# 07_-_FPGA_XCVR.net
KiCad netlist of a schematic drawn in Altium Designer
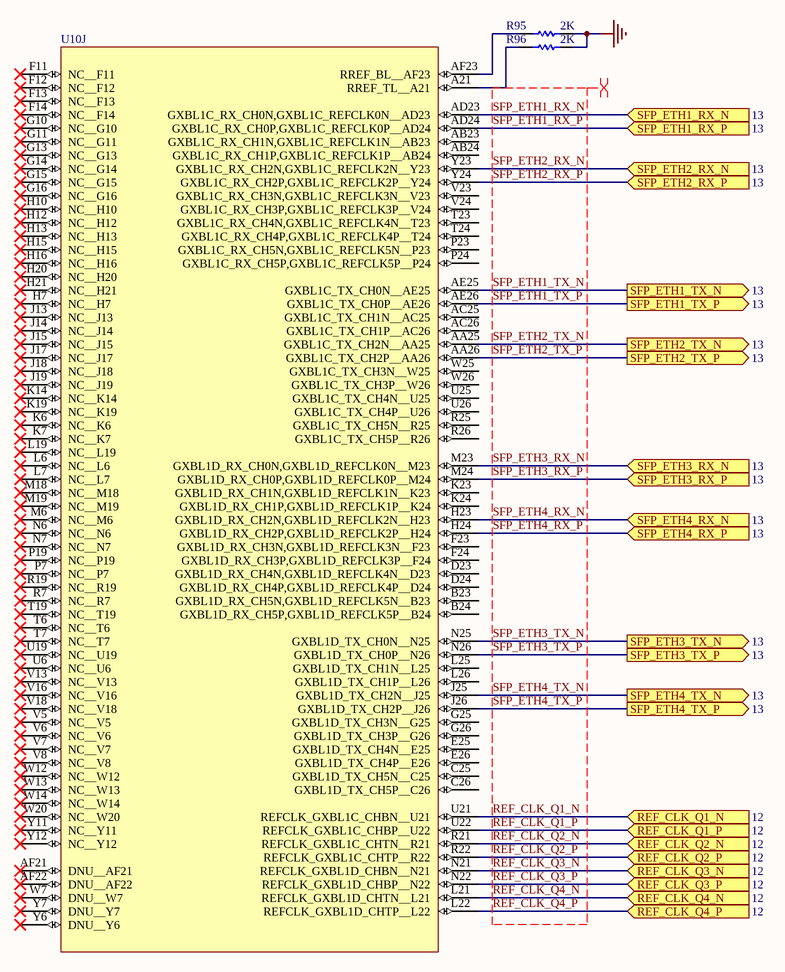
[diagram p0: [07] - FPGA XCVR.SchDoc]

(export (version "E")
  (design (tool "Eeschema 10.0.6"))
  (components
    (comp (ref "R95")
      (value "2K")
      (footprint "0402_R")
      (description "SMD Resistor")
      (fields (field (name "TOLERANCE") "1%"))
      (libsource (lib "Passive Components") (part "Res SMD"))
    )
    (comp (ref "R96")
      (value "2K")
      (footprint "0402_R")
      (description "SMD Resistor")
      (fields (field (name "TOLERANCE") "1%"))
      (libsource (lib "Passive Components") (part "Res SMD"))
    )
    (comp (ref "U10")
      (value "10AX016 F27")
      (footprint "FBGA672")
      (libsource (lib "Project_schlib") (part "10AX016"))
    )
  )
  (nets
    (net (code "1") (name "/REF_CLK_Q1_N") (class "Default")
      (node (ref "U10") (pin "U21") (pinfunction "REFCLK_GXBL1C_CHBN__U21_U21") (pintype "bidirectional"))
    )
    (net (code "2") (name "/REF_CLK_Q1_P") (class "Default")
      (node (ref "U10") (pin "U22") (pinfunction "REFCLK_GXBL1C_CHBP__U22_U22") (pintype "bidirectional"))
    )
    (net (code "3") (name "/REF_CLK_Q2_N") (class "Default")
      (node (ref "U10") (pin "R21") (pinfunction "REFCLK_GXBL1C_CHTN__R21_R21") (pintype "bidirectional"))
    )
    (net (code "4") (name "/REF_CLK_Q2_P") (class "Default")
      (node (ref "U10") (pin "R22") (pinfunction "REFCLK_GXBL1C_CHTP__R22_R22") (pintype "bidirectional"))
    )
    (net (code "5") (name "/REF_CLK_Q3_N") (class "Default")
      (node (ref "U10") (pin "N21") (pinfunction "REFCLK_GXBL1D_CHBN__N21_N21") (pintype "bidirectional"))
    )
    (net (code "6") (name "/REF_CLK_Q3_P") (class "Default")
      (node (ref "U10") (pin "N22") (pinfunction "REFCLK_GXBL1D_CHBP__N22_N22") (pintype "bidirectional"))
    )
    (net (code "7") (name "/REF_CLK_Q4_N") (class "Default")
      (node (ref "U10") (pin "L21") (pinfunction "REFCLK_GXBL1D_CHTN__L21_L21") (pintype "bidirectional"))
    )
    (net (code "8") (name "/REF_CLK_Q4_P") (class "Default")
      (node (ref "U10") (pin "L22") (pinfunction "REFCLK_GXBL1D_CHTP__L22_L22") (pintype "bidirectional"))
    )
    (net (code "9") (name "/SFP_ETH1_RX_N") (class "Default")
      (node (ref "U10") (pin "AD23") (pinfunction "GXBL1C_RX_CH0N,GXBL1C_REFCLK0N__AD23_AD23") (pintype "bidirectional"))
    )
    (net (code "10") (name "/SFP_ETH1_RX_P") (class "Default")
      (node (ref "U10") (pin "AD24") (pinfunction "GXBL1C_RX_CH0P,GXBL1C_REFCLK0P__AD24_AD24") (pintype "bidirectional"))
    )
    (net (code "11") (name "/SFP_ETH1_TX_N") (class "Default")
      (node (ref "U10") (pin "AE25") (pinfunction "GXBL1C_TX_CH0N__AE25_AE25") (pintype "bidirectional"))
    )
    (net (code "12") (name "/SFP_ETH1_TX_P") (class "Default")
      (node (ref "U10") (pin "AE26") (pinfunction "GXBL1C_TX_CH0P__AE26_AE26") (pintype "bidirectional"))
    )
    (net (code "13") (name "/SFP_ETH2_RX_N") (class "Default")
      (node (ref "U10") (pin "Y23") (pinfunction "GXBL1C_RX_CH2N,GXBL1C_REFCLK2N__Y23_Y23") (pintype "bidirectional"))
    )
    (net (code "14") (name "/SFP_ETH2_RX_P") (class "Default")
      (node (ref "U10") (pin "Y24") (pinfunction "GXBL1C_RX_CH2P,GXBL1C_REFCLK2P__Y24_Y24") (pintype "bidirectional"))
    )
    (net (code "15") (name "/SFP_ETH2_TX_N") (class "Default")
      (node (ref "U10") (pin "AA25") (pinfunction "GXBL1C_TX_CH2N__AA25_AA25") (pintype "bidirectional"))
    )
    (net (code "16") (name "/SFP_ETH2_TX_P") (class "Default")
      (node (ref "U10") (pin "AA26") (pinfunction "GXBL1C_TX_CH2P__AA26_AA26") (pintype "bidirectional"))
    )
    (net (code "17") (name "/SFP_ETH3_RX_N") (class "Default")
      (node (ref "U10") (pin "M23") (pinfunction "GXBL1D_RX_CH0N,GXBL1D_REFCLK0N__M23_M23") (pintype "bidirectional"))
    )
    (net (code "18") (name "/SFP_ETH3_RX_P") (class "Default")
      (node (ref "U10") (pin "M24") (pinfunction "GXBL1D_RX_CH0P,GXBL1D_REFCLK0P__M24_M24") (pintype "bidirectional"))
    )
    (net (code "19") (name "/SFP_ETH3_TX_N") (class "Default")
      (node (ref "U10") (pin "N25") (pinfunction "GXBL1D_TX_CH0N__N25_N25") (pintype "bidirectional"))
    )
    (net (code "20") (name "/SFP_ETH3_TX_P") (class "Default")
      (node (ref "U10") (pin "N26") (pinfunction "GXBL1D_TX_CH0P__N26_N26") (pintype "bidirectional"))
    )
    (net (code "21") (name "/SFP_ETH4_RX_N") (class "Default")
      (node (ref "U10") (pin "H23") (pinfunction "GXBL1D_RX_CH2N,GXBL1D_REFCLK2N__H23_H23") (pintype "bidirectional"))
    )
    (net (code "22") (name "/SFP_ETH4_RX_P") (class "Default")
      (node (ref "U10") (pin "H24") (pinfunction "GXBL1D_RX_CH2P,GXBL1D_REFCLK2P__H24_H24") (pintype "bidirectional"))
    )
    (net (code "23") (name "/SFP_ETH4_TX_N") (class "Default")
      (node (ref "U10") (pin "J25") (pinfunction "GXBL1D_TX_CH2N__J25_J25") (pintype "bidirectional"))
    )
    (net (code "24") (name "/SFP_ETH4_TX_P") (class "Default")
      (node (ref "U10") (pin "J26") (pinfunction "GXBL1D_TX_CH2P__J26_J26") (pintype "bidirectional"))
    )
    (net (code "25") (name "GND") (class "Default")
      (node (ref "R95") (pin "2") (pinfunction "2_2") (pintype "passive"))
      (node (ref "R96") (pin "2") (pinfunction "2_2") (pintype "passive"))
    )
    (net (code "26") (name "Net-(U10J-RREF_BL__AF23)") (class "Default")
      (node (ref "R95") (pin "1") (pinfunction "1_1") (pintype "passive"))
      (node (ref "U10") (pin "AF23") (pinfunction "RREF_BL__AF23_AF23") (pintype "bidirectional"))
    )
    (net (code "27") (name "Net-(U10J-RREF_TL__A21)") (class "Default")
      (node (ref "R96") (pin "1") (pinfunction "1_1") (pintype "passive"))
      (node (ref "U10") (pin "A21") (pinfunction "RREF_TL__A21_A21") (pintype "bidirectional"))
    )
    (net (code "28") (name "unconnected-(U10J-DNU__AF21-PadAF21)") (class "Default")
      (node (ref "U10") (pin "AF21") (pinfunction "DNU__AF21_AF21") (pintype "bidirectional+no_connect"))
    )
    (net (code "29") (name "unconnected-(U10J-DNU__AF22-PadAF22)") (class "Default")
      (node (ref "U10") (pin "AF22") (pinfunction "DNU__AF22_AF22") (pintype "bidirectional+no_connect"))
    )
    (net (code "30") (name "unconnected-(U10J-DNU__W7-PadW7)") (class "Default")
      (node (ref "U10") (pin "W7") (pinfunction "DNU__W7_W7") (pintype "bidirectional+no_connect"))
    )
    (net (code "31") (name "unconnected-(U10J-DNU__Y6-PadY6)") (class "Default")
      (node (ref "U10") (pin "Y6") (pinfunction "DNU__Y6_Y6") (pintype "bidirectional+no_connect"))
    )
    (net (code "32") (name "unconnected-(U10J-DNU__Y7-PadY7)") (class "Default")
      (node (ref "U10") (pin "Y7") (pinfunction "DNU__Y7_Y7") (pintype "bidirectional+no_connect"))
    )
    (net (code "33") (name "unconnected-(U10J-GXBL1C_RX_CH1N,GXBL1C_REFCLK1N__AB23-PadAB23)") (class "Default")
      (node (ref "U10") (pin "AB23") (pinfunction "GXBL1C_RX_CH1N,GXBL1C_REFCLK1N__AB23_AB23") (pintype "bidirectional"))
    )
    (net (code "34") (name "unconnected-(U10J-GXBL1C_RX_CH1P,GXBL1C_REFCLK1P__AB24-PadAB24)") (class "Default")
      (node (ref "U10") (pin "AB24") (pinfunction "GXBL1C_RX_CH1P,GXBL1C_REFCLK1P__AB24_AB24") (pintype "bidirectional"))
    )
    (net (code "35") (name "unconnected-(U10J-GXBL1C_RX_CH3N,GXBL1C_REFCLK3N__V23-PadV23)") (class "Default")
      (node (ref "U10") (pin "V23") (pinfunction "GXBL1C_RX_CH3N,GXBL1C_REFCLK3N__V23_V23") (pintype "bidirectional"))
    )
    (net (code "36") (name "unconnected-(U10J-GXBL1C_RX_CH3P,GXBL1C_REFCLK3P__V24-PadV24)") (class "Default")
      (node (ref "U10") (pin "V24") (pinfunction "GXBL1C_RX_CH3P,GXBL1C_REFCLK3P__V24_V24") (pintype "bidirectional"))
    )
    (net (code "37") (name "unconnected-(U10J-GXBL1C_RX_CH4N,GXBL1C_REFCLK4N__T23-PadT23)") (class "Default")
      (node (ref "U10") (pin "T23") (pinfunction "GXBL1C_RX_CH4N,GXBL1C_REFCLK4N__T23_T23") (pintype "bidirectional"))
    )
    (net (code "38") (name "unconnected-(U10J-GXBL1C_RX_CH4P,GXBL1C_REFCLK4P__T24-PadT24)") (class "Default")
      (node (ref "U10") (pin "T24") (pinfunction "GXBL1C_RX_CH4P,GXBL1C_REFCLK4P__T24_T24") (pintype "bidirectional"))
    )
    (net (code "39") (name "unconnected-(U10J-GXBL1C_RX_CH5N,GXBL1C_REFCLK5N__P23-PadP23)") (class "Default")
      (node (ref "U10") (pin "P23") (pinfunction "GXBL1C_RX_CH5N,GXBL1C_REFCLK5N__P23_P23") (pintype "bidirectional"))
    )
    (net (code "40") (name "unconnected-(U10J-GXBL1C_RX_CH5P,GXBL1C_REFCLK5P__P24-PadP24)") (class "Default")
      (node (ref "U10") (pin "P24") (pinfunction "GXBL1C_RX_CH5P,GXBL1C_REFCLK5P__P24_P24") (pintype "bidirectional"))
    )
    (net (code "41") (name "unconnected-(U10J-GXBL1C_TX_CH1N__AC25-PadAC25)") (class "Default")
      (node (ref "U10") (pin "AC25") (pinfunction "GXBL1C_TX_CH1N__AC25_AC25") (pintype "bidirectional"))
    )
    (net (code "42") (name "unconnected-(U10J-GXBL1C_TX_CH1P__AC26-PadAC26)") (class "Default")
      (node (ref "U10") (pin "AC26") (pinfunction "GXBL1C_TX_CH1P__AC26_AC26") (pintype "bidirectional"))
    )
    (net (code "43") (name "unconnected-(U10J-GXBL1C_TX_CH3N__W25-PadW25)") (class "Default")
      (node (ref "U10") (pin "W25") (pinfunction "GXBL1C_TX_CH3N__W25_W25") (pintype "bidirectional"))
    )
    (net (code "44") (name "unconnected-(U10J-GXBL1C_TX_CH3P__W26-PadW26)") (class "Default")
      (node (ref "U10") (pin "W26") (pinfunction "GXBL1C_TX_CH3P__W26_W26") (pintype "bidirectional"))
    )
    (net (code "45") (name "unconnected-(U10J-GXBL1C_TX_CH4N__U25-PadU25)") (class "Default")
      (node (ref "U10") (pin "U25") (pinfunction "GXBL1C_TX_CH4N__U25_U25") (pintype "bidirectional"))
    )
    (net (code "46") (name "unconnected-(U10J-GXBL1C_TX_CH4P__U26-PadU26)") (class "Default")
      (node (ref "U10") (pin "U26") (pinfunction "GXBL1C_TX_CH4P__U26_U26") (pintype "bidirectional"))
    )
    (net (code "47") (name "unconnected-(U10J-GXBL1C_TX_CH5N__R25-PadR25)") (class "Default")
      (node (ref "U10") (pin "R25") (pinfunction "GXBL1C_TX_CH5N__R25_R25") (pintype "bidirectional"))
    )
    (net (code "48") (name "unconnected-(U10J-GXBL1C_TX_CH5P__R26-PadR26)") (class "Default")
      (node (ref "U10") (pin "R26") (pinfunction "GXBL1C_TX_CH5P__R26_R26") (pintype "bidirectional"))
    )
    (net (code "49") (name "unconnected-(U10J-GXBL1D_RX_CH1N,GXBL1D_REFCLK1N__K23-PadK23)") (class "Default")
      (node (ref "U10") (pin "K23") (pinfunction "GXBL1D_RX_CH1N,GXBL1D_REFCLK1N__K23_K23") (pintype "bidirectional"))
    )
    (net (code "50") (name "unconnected-(U10J-GXBL1D_RX_CH1P,GXBL1D_REFCLK1P__K24-PadK24)") (class "Default")
      (node (ref "U10") (pin "K24") (pinfunction "GXBL1D_RX_CH1P,GXBL1D_REFCLK1P__K24_K24") (pintype "bidirectional"))
    )
    (net (code "51") (name "unconnected-(U10J-GXBL1D_RX_CH3N,GXBL1D_REFCLK3N__F23-PadF23)") (class "Default")
      (node (ref "U10") (pin "F23") (pinfunction "GXBL1D_RX_CH3N,GXBL1D_REFCLK3N__F23_F23") (pintype "bidirectional"))
    )
    (net (code "52") (name "unconnected-(U10J-GXBL1D_RX_CH3P,GXBL1D_REFCLK3P__F24-PadF24)") (class "Default")
      (node (ref "U10") (pin "F24") (pinfunction "GXBL1D_RX_CH3P,GXBL1D_REFCLK3P__F24_F24") (pintype "bidirectional"))
    )
    (net (code "53") (name "unconnected-(U10J-GXBL1D_RX_CH4N,GXBL1D_REFCLK4N__D23-PadD23)") (class "Default")
      (node (ref "U10") (pin "D23") (pinfunction "GXBL1D_RX_CH4N,GXBL1D_REFCLK4N__D23_D23") (pintype "bidirectional"))
    )
    (net (code "54") (name "unconnected-(U10J-GXBL1D_RX_CH4P,GXBL1D_REFCLK4P__D24-PadD24)") (class "Default")
      (node (ref "U10") (pin "D24") (pinfunction "GXBL1D_RX_CH4P,GXBL1D_REFCLK4P__D24_D24") (pintype "bidirectional"))
    )
    (net (code "55") (name "unconnected-(U10J-GXBL1D_RX_CH5N,GXBL1D_REFCLK5N__B23-PadB23)") (class "Default")
      (node (ref "U10") (pin "B23") (pinfunction "GXBL1D_RX_CH5N,GXBL1D_REFCLK5N__B23_B23") (pintype "bidirectional"))
    )
    (net (code "56") (name "unconnected-(U10J-GXBL1D_RX_CH5P,GXBL1D_REFCLK5P__B24-PadB24)") (class "Default")
      (node (ref "U10") (pin "B24") (pinfunction "GXBL1D_RX_CH5P,GXBL1D_REFCLK5P__B24_B24") (pintype "bidirectional"))
    )
    (net (code "57") (name "unconnected-(U10J-GXBL1D_TX_CH1N__L25-PadL25)") (class "Default")
      (node (ref "U10") (pin "L25") (pinfunction "GXBL1D_TX_CH1N__L25_L25") (pintype "bidirectional"))
    )
    (net (code "58") (name "unconnected-(U10J-GXBL1D_TX_CH1P__L26-PadL26)") (class "Default")
      (node (ref "U10") (pin "L26") (pinfunction "GXBL1D_TX_CH1P__L26_L26") (pintype "bidirectional"))
    )
    (net (code "59") (name "unconnected-(U10J-GXBL1D_TX_CH3N__G25-PadG25)") (class "Default")
      (node (ref "U10") (pin "G25") (pinfunction "GXBL1D_TX_CH3N__G25_G25") (pintype "bidirectional"))
    )
    (net (code "60") (name "unconnected-(U10J-GXBL1D_TX_CH3P__G26-PadG26)") (class "Default")
      (node (ref "U10") (pin "G26") (pinfunction "GXBL1D_TX_CH3P__G26_G26") (pintype "bidirectional"))
    )
    (net (code "61") (name "unconnected-(U10J-GXBL1D_TX_CH4N__E25-PadE25)") (class "Default")
      (node (ref "U10") (pin "E25") (pinfunction "GXBL1D_TX_CH4N__E25_E25") (pintype "bidirectional"))
    )
    (net (code "62") (name "unconnected-(U10J-GXBL1D_TX_CH4P__E26-PadE26)") (class "Default")
      (node (ref "U10") (pin "E26") (pinfunction "GXBL1D_TX_CH4P__E26_E26") (pintype "bidirectional"))
    )
    (net (code "63") (name "unconnected-(U10J-GXBL1D_TX_CH5N__C25-PadC25)") (class "Default")
      (node (ref "U10") (pin "C25") (pinfunction "GXBL1D_TX_CH5N__C25_C25") (pintype "bidirectional"))
    )
    (net (code "64") (name "unconnected-(U10J-GXBL1D_TX_CH5P__C26-PadC26)") (class "Default")
      (node (ref "U10") (pin "C26") (pinfunction "GXBL1D_TX_CH5P__C26_C26") (pintype "bidirectional"))
    )
    (net (code "65") (name "unconnected-(U10J-NC__F11-PadF11)") (class "Default")
      (node (ref "U10") (pin "F11") (pinfunction "NC__F11_F11") (pintype "bidirectional+no_connect"))
    )
    (net (code "66") (name "unconnected-(U10J-NC__F12-PadF12)") (class "Default")
      (node (ref "U10") (pin "F12") (pinfunction "NC__F12_F12") (pintype "bidirectional+no_connect"))
    )
    (net (code "67") (name "unconnected-(U10J-NC__F13-PadF13)") (class "Default")
      (node (ref "U10") (pin "F13") (pinfunction "NC__F13_F13") (pintype "bidirectional+no_connect"))
    )
    (net (code "68") (name "unconnected-(U10J-NC__F14-PadF14)") (class "Default")
      (node (ref "U10") (pin "F14") (pinfunction "NC__F14_F14") (pintype "bidirectional+no_connect"))
    )
    (net (code "69") (name "unconnected-(U10J-NC__G10-PadG10)") (class "Default")
      (node (ref "U10") (pin "G10") (pinfunction "NC__G10_G10") (pintype "bidirectional+no_connect"))
    )
    (net (code "70") (name "unconnected-(U10J-NC__G11-PadG11)") (class "Default")
      (node (ref "U10") (pin "G11") (pinfunction "NC__G11_G11") (pintype "bidirectional+no_connect"))
    )
    (net (code "71") (name "unconnected-(U10J-NC__G13-PadG13)") (class "Default")
      (node (ref "U10") (pin "G13") (pinfunction "NC__G13_G13") (pintype "bidirectional+no_connect"))
    )
    (net (code "72") (name "unconnected-(U10J-NC__G14-PadG14)") (class "Default")
      (node (ref "U10") (pin "G14") (pinfunction "NC__G14_G14") (pintype "bidirectional+no_connect"))
    )
    (net (code "73") (name "unconnected-(U10J-NC__G15-PadG15)") (class "Default")
      (node (ref "U10") (pin "G15") (pinfunction "NC__G15_G15") (pintype "bidirectional+no_connect"))
    )
    (net (code "74") (name "unconnected-(U10J-NC__G16-PadG16)") (class "Default")
      (node (ref "U10") (pin "G16") (pinfunction "NC__G16_G16") (pintype "bidirectional+no_connect"))
    )
    (net (code "75") (name "unconnected-(U10J-NC__H7-PadH7)") (class "Default")
      (node (ref "U10") (pin "H7") (pinfunction "NC__H7_H7") (pintype "bidirectional+no_connect"))
    )
    (net (code "76") (name "unconnected-(U10J-NC__H10-PadH10)") (class "Default")
      (node (ref "U10") (pin "H10") (pinfunction "NC__H10_H10") (pintype "bidirectional+no_connect"))
    )
    (net (code "77") (name "unconnected-(U10J-NC__H12-PadH12)") (class "Default")
      (node (ref "U10") (pin "H12") (pinfunction "NC__H12_H12") (pintype "bidirectional+no_connect"))
    )
    (net (code "78") (name "unconnected-(U10J-NC__H13-PadH13)") (class "Default")
      (node (ref "U10") (pin "H13") (pinfunction "NC__H13_H13") (pintype "bidirectional+no_connect"))
    )
    (net (code "79") (name "unconnected-(U10J-NC__H15-PadH15)") (class "Default")
      (node (ref "U10") (pin "H15") (pinfunction "NC__H15_H15") (pintype "bidirectional+no_connect"))
    )
    (net (code "80") (name "unconnected-(U10J-NC__H16-PadH16)") (class "Default")
      (node (ref "U10") (pin "H16") (pinfunction "NC__H16_H16") (pintype "bidirectional+no_connect"))
    )
    (net (code "81") (name "unconnected-(U10J-NC__H20-PadH20)") (class "Default")
      (node (ref "U10") (pin "H20") (pinfunction "NC__H20_H20") (pintype "bidirectional+no_connect"))
    )
    (net (code "82") (name "unconnected-(U10J-NC__H21-PadH21)") (class "Default")
      (node (ref "U10") (pin "H21") (pinfunction "NC__H21_H21") (pintype "bidirectional+no_connect"))
    )
    (net (code "83") (name "unconnected-(U10J-NC__J13-PadJ13)") (class "Default")
      (node (ref "U10") (pin "J13") (pinfunction "NC__J13_J13") (pintype "bidirectional+no_connect"))
    )
    (net (code "84") (name "unconnected-(U10J-NC__J14-PadJ14)") (class "Default")
      (node (ref "U10") (pin "J14") (pinfunction "NC__J14_J14") (pintype "bidirectional+no_connect"))
    )
    (net (code "85") (name "unconnected-(U10J-NC__J15-PadJ15)") (class "Default")
      (node (ref "U10") (pin "J15") (pinfunction "NC__J15_J15") (pintype "bidirectional+no_connect"))
    )
    (net (code "86") (name "unconnected-(U10J-NC__J17-PadJ17)") (class "Default")
      (node (ref "U10") (pin "J17") (pinfunction "NC__J17_J17") (pintype "bidirectional+no_connect"))
    )
    (net (code "87") (name "unconnected-(U10J-NC__J18-PadJ18)") (class "Default")
      (node (ref "U10") (pin "J18") (pinfunction "NC__J18_J18") (pintype "bidirectional+no_connect"))
    )
    (net (code "88") (name "unconnected-(U10J-NC__J19-PadJ19)") (class "Default")
      (node (ref "U10") (pin "J19") (pinfunction "NC__J19_J19") (pintype "bidirectional+no_connect"))
    )
    (net (code "89") (name "unconnected-(U10J-NC__K6-PadK6)") (class "Default")
      (node (ref "U10") (pin "K6") (pinfunction "NC__K6_K6") (pintype "bidirectional+no_connect"))
    )
    (net (code "90") (name "unconnected-(U10J-NC__K7-PadK7)") (class "Default")
      (node (ref "U10") (pin "K7") (pinfunction "NC__K7_K7") (pintype "bidirectional+no_connect"))
    )
    (net (code "91") (name "unconnected-(U10J-NC__K14-PadK14)") (class "Default")
      (node (ref "U10") (pin "K14") (pinfunction "NC__K14_K14") (pintype "bidirectional+no_connect"))
    )
    (net (code "92") (name "unconnected-(U10J-NC__K19-PadK19)") (class "Default")
      (node (ref "U10") (pin "K19") (pinfunction "NC__K19_K19") (pintype "bidirectional+no_connect"))
    )
    (net (code "93") (name "unconnected-(U10J-NC__L6-PadL6)") (class "Default")
      (node (ref "U10") (pin "L6") (pinfunction "NC__L6_L6") (pintype "bidirectional+no_connect"))
    )
    (net (code "94") (name "unconnected-(U10J-NC__L7-PadL7)") (class "Default")
      (node (ref "U10") (pin "L7") (pinfunction "NC__L7_L7") (pintype "bidirectional+no_connect"))
    )
    (net (code "95") (name "unconnected-(U10J-NC__L19-PadL19)") (class "Default")
      (node (ref "U10") (pin "L19") (pinfunction "NC__L19_L19") (pintype "bidirectional+no_connect"))
    )
    (net (code "96") (name "unconnected-(U10J-NC__M6-PadM6)") (class "Default")
      (node (ref "U10") (pin "M6") (pinfunction "NC__M6_M6") (pintype "bidirectional+no_connect"))
    )
    (net (code "97") (name "unconnected-(U10J-NC__M18-PadM18)") (class "Default")
      (node (ref "U10") (pin "M18") (pinfunction "NC__M18_M18") (pintype "bidirectional+no_connect"))
    )
    (net (code "98") (name "unconnected-(U10J-NC__M19-PadM19)") (class "Default")
      (node (ref "U10") (pin "M19") (pinfunction "NC__M19_M19") (pintype "bidirectional+no_connect"))
    )
    (net (code "99") (name "unconnected-(U10J-NC__N6-PadN6)") (class "Default")
      (node (ref "U10") (pin "N6") (pinfunction "NC__N6_N6") (pintype "bidirectional+no_connect"))
    )
    (net (code "100") (name "unconnected-(U10J-NC__N7-PadN7)") (class "Default")
      (node (ref "U10") (pin "N7") (pinfunction "NC__N7_N7") (pintype "bidirectional+no_connect"))
    )
    (net (code "101") (name "unconnected-(U10J-NC__P7-PadP7)") (class "Default")
      (node (ref "U10") (pin "P7") (pinfunction "NC__P7_P7") (pintype "bidirectional+no_connect"))
    )
    (net (code "102") (name "unconnected-(U10J-NC__P19-PadP19)") (class "Default")
      (node (ref "U10") (pin "P19") (pinfunction "NC__P19_P19") (pintype "bidirectional+no_connect"))
    )
    (net (code "103") (name "unconnected-(U10J-NC__R7-PadR7)") (class "Default")
      (node (ref "U10") (pin "R7") (pinfunction "NC__R7_R7") (pintype "bidirectional+no_connect"))
    )
    (net (code "104") (name "unconnected-(U10J-NC__R19-PadR19)") (class "Default")
      (node (ref "U10") (pin "R19") (pinfunction "NC__R19_R19") (pintype "bidirectional+no_connect"))
    )
    (net (code "105") (name "unconnected-(U10J-NC__T6-PadT6)") (class "Default")
      (node (ref "U10") (pin "T6") (pinfunction "NC__T6_T6") (pintype "bidirectional+no_connect"))
    )
    (net (code "106") (name "unconnected-(U10J-NC__T7-PadT7)") (class "Default")
      (node (ref "U10") (pin "T7") (pinfunction "NC__T7_T7") (pintype "bidirectional+no_connect"))
    )
    (net (code "107") (name "unconnected-(U10J-NC__T19-PadT19)") (class "Default")
      (node (ref "U10") (pin "T19") (pinfunction "NC__T19_T19") (pintype "bidirectional+no_connect"))
    )
    (net (code "108") (name "unconnected-(U10J-NC__U6-PadU6)") (class "Default")
      (node (ref "U10") (pin "U6") (pinfunction "NC__U6_U6") (pintype "bidirectional+no_connect"))
    )
    (net (code "109") (name "unconnected-(U10J-NC__U19-PadU19)") (class "Default")
      (node (ref "U10") (pin "U19") (pinfunction "NC__U19_U19") (pintype "bidirectional+no_connect"))
    )
    (net (code "110") (name "unconnected-(U10J-NC__V5-PadV5)") (class "Default")
      (node (ref "U10") (pin "V5") (pinfunction "NC__V5_V5") (pintype "bidirectional+no_connect"))
    )
    (net (code "111") (name "unconnected-(U10J-NC__V6-PadV6)") (class "Default")
      (node (ref "U10") (pin "V6") (pinfunction "NC__V6_V6") (pintype "bidirectional+no_connect"))
    )
    (net (code "112") (name "unconnected-(U10J-NC__V7-PadV7)") (class "Default")
      (node (ref "U10") (pin "V7") (pinfunction "NC__V7_V7") (pintype "bidirectional+no_connect"))
    )
    (net (code "113") (name "unconnected-(U10J-NC__V8-PadV8)") (class "Default")
      (node (ref "U10") (pin "V8") (pinfunction "NC__V8_V8") (pintype "bidirectional+no_connect"))
    )
    (net (code "114") (name "unconnected-(U10J-NC__V13-PadV13)") (class "Default")
      (node (ref "U10") (pin "V13") (pinfunction "NC__V13_V13") (pintype "bidirectional+no_connect"))
    )
    (net (code "115") (name "unconnected-(U10J-NC__V16-PadV16)") (class "Default")
      (node (ref "U10") (pin "V16") (pinfunction "NC__V16_V16") (pintype "bidirectional+no_connect"))
    )
    (net (code "116") (name "unconnected-(U10J-NC__V18-PadV18)") (class "Default")
      (node (ref "U10") (pin "V18") (pinfunction "NC__V18_V18") (pintype "bidirectional+no_connect"))
    )
    (net (code "117") (name "unconnected-(U10J-NC__W12-PadW12)") (class "Default")
      (node (ref "U10") (pin "W12") (pinfunction "NC__W12_W12") (pintype "bidirectional+no_connect"))
    )
    (net (code "118") (name "unconnected-(U10J-NC__W13-PadW13)") (class "Default")
      (node (ref "U10") (pin "W13") (pinfunction "NC__W13_W13") (pintype "bidirectional+no_connect"))
    )
    (net (code "119") (name "unconnected-(U10J-NC__W14-PadW14)") (class "Default")
      (node (ref "U10") (pin "W14") (pinfunction "NC__W14_W14") (pintype "bidirectional+no_connect"))
    )
    (net (code "120") (name "unconnected-(U10J-NC__W20-PadW20)") (class "Default")
      (node (ref "U10") (pin "W20") (pinfunction "NC__W20_W20") (pintype "bidirectional+no_connect"))
    )
    (net (code "121") (name "unconnected-(U10J-NC__Y11-PadY11)") (class "Default")
      (node (ref "U10") (pin "Y11") (pinfunction "NC__Y11_Y11") (pintype "bidirectional+no_connect"))
    )
    (net (code "122") (name "unconnected-(U10J-NC__Y12-PadY12)") (class "Default")
      (node (ref "U10") (pin "Y12") (pinfunction "NC__Y12_Y12") (pintype "bidirectional+no_connect"))
    )
  )
)
